# ETHERNET_PHY1.net
KiCad netlist of a schematic drawn in Altium Designer
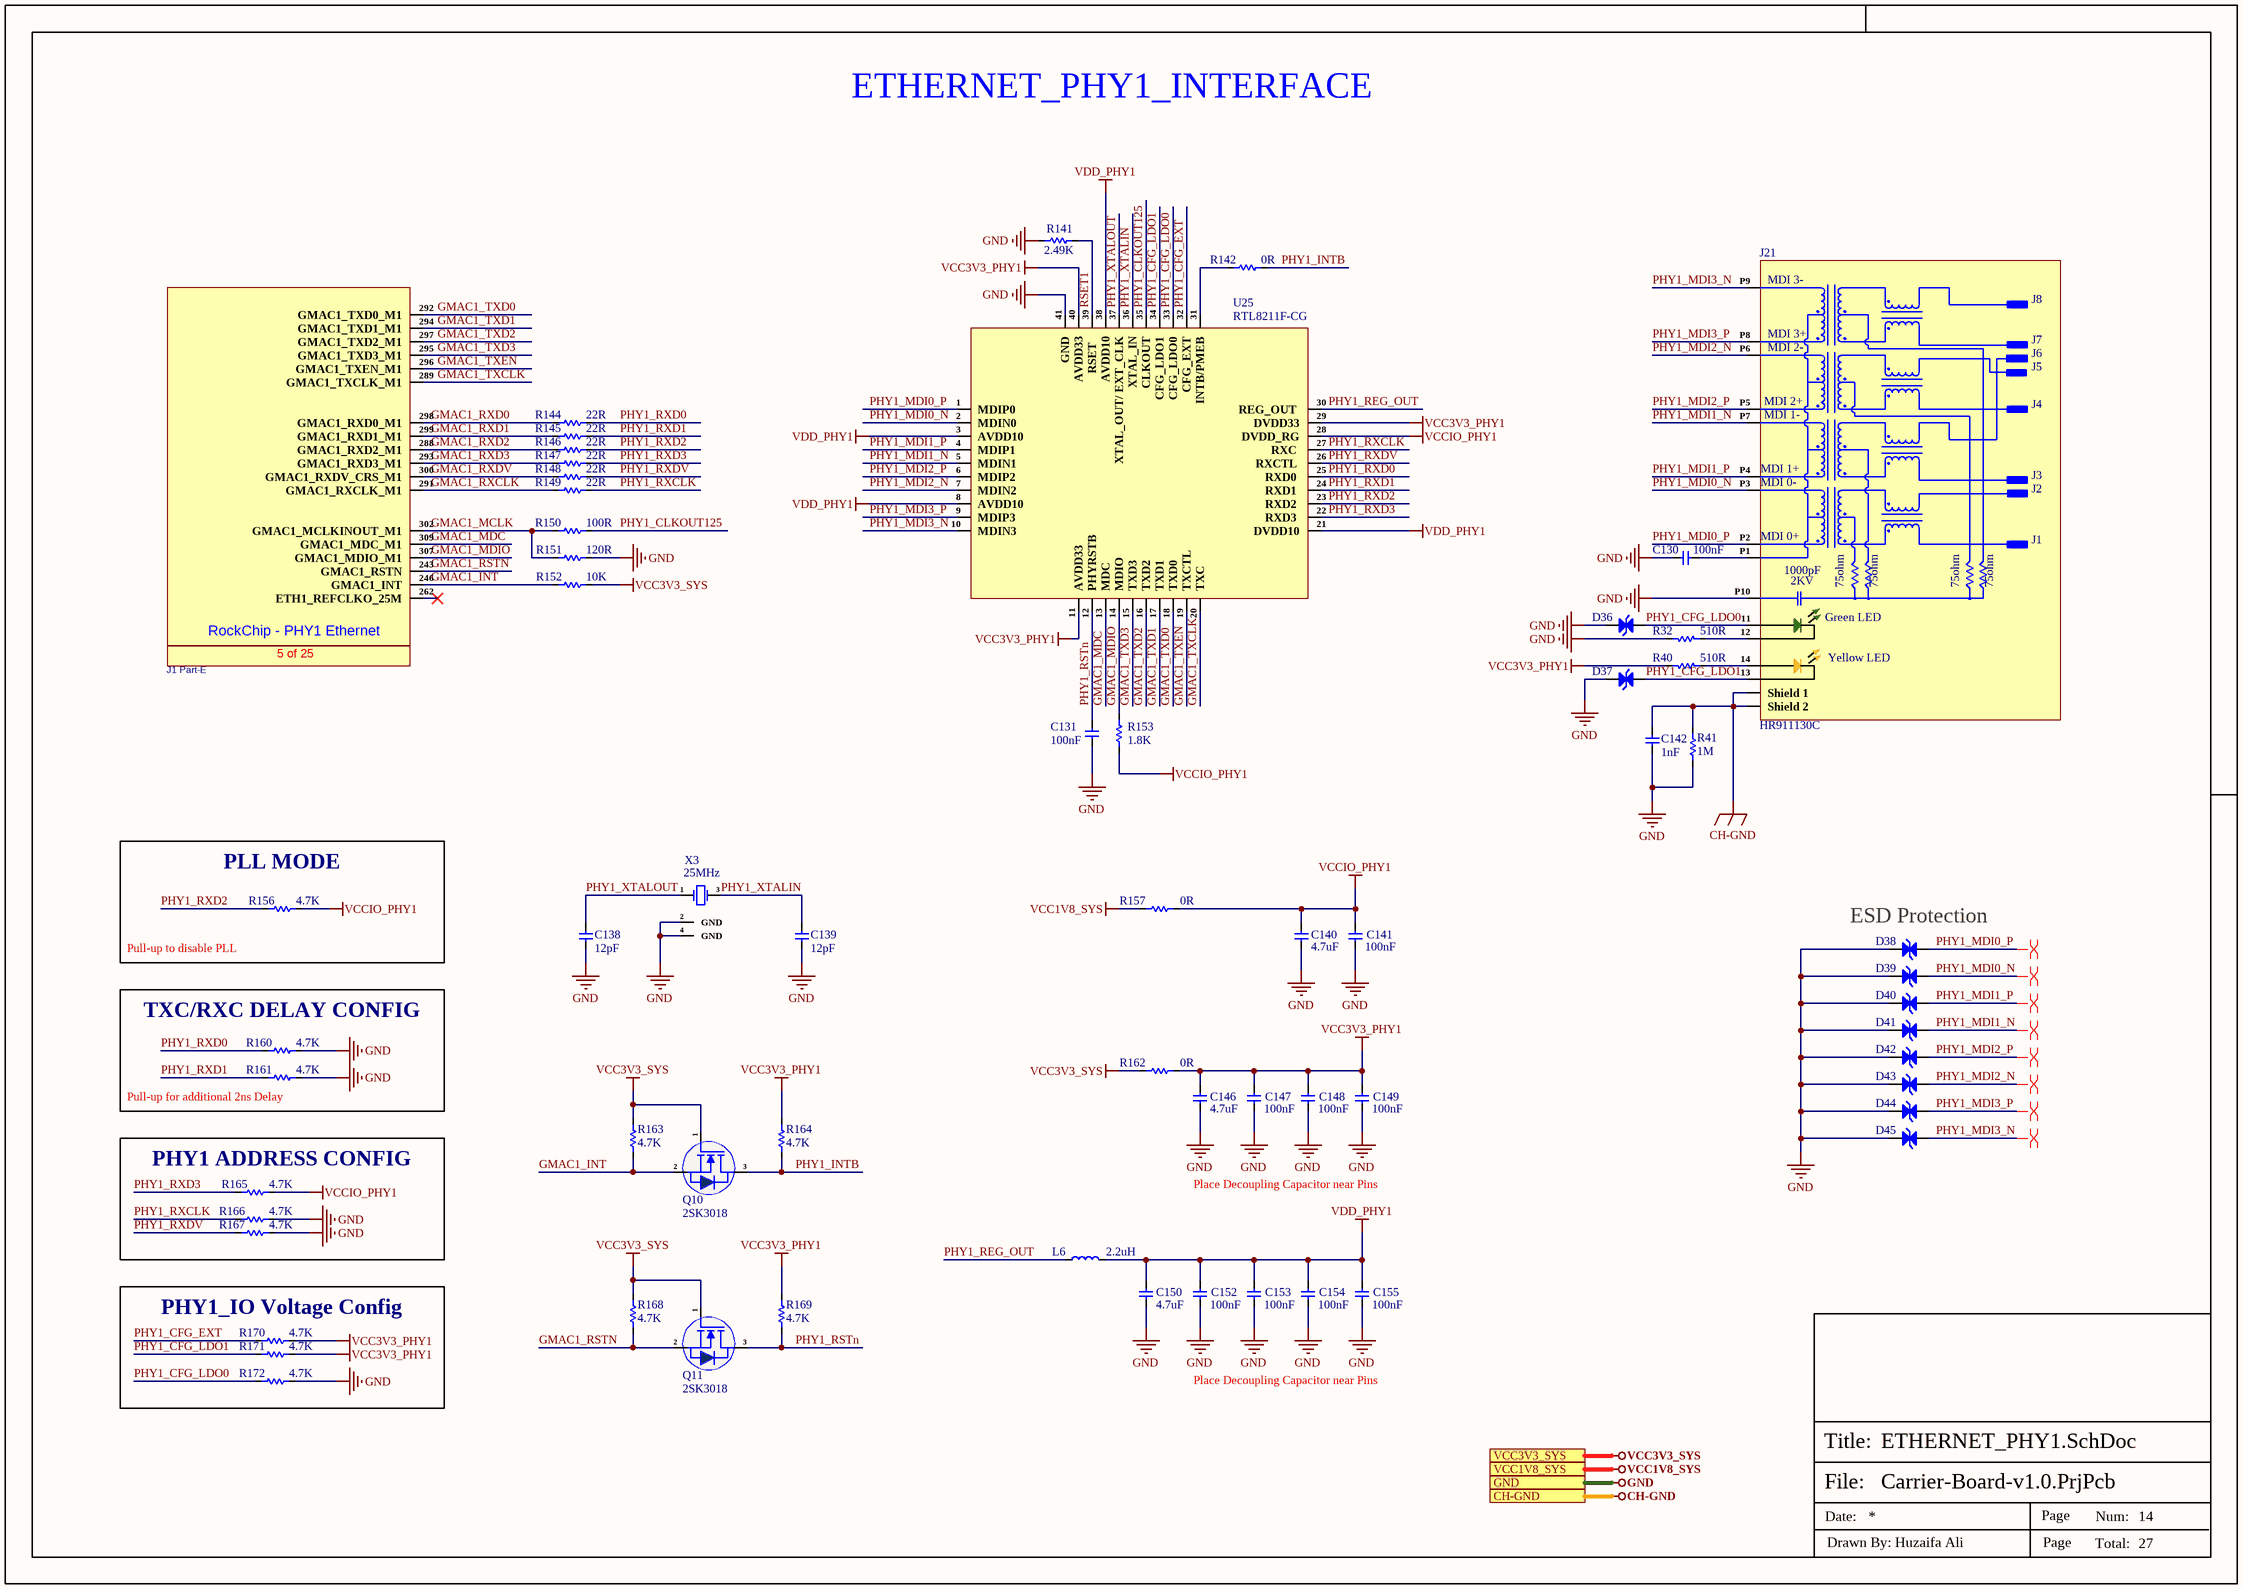
[diagram p0: ETHERNET_PHY1.SchDoc]

(export (version "E")
  (design (tool "Eeschema 10.0.6"))
  (components
    (comp (ref "C130")
      (value "100nF")
      (footprint "cap-0402")
      (description "CAP CER 0.1UF 50V X7R 0402")
      (fields
        (field (name "MANUFACTURER") "TDK")
        (field (name "MANUFACTURER PART NUMBER") "C1005X7R1H104KT000F")
      )
      (libsource (lib "eSpark Libraries") (part "C1005X7R1H104KT000F"))
    )
    (comp (ref "C131")
      (value "100nF")
      (footprint "Cap-0402")
      (description "CAP CER 0.1UF 16V X5R 0402")
      (fields
        (field (name "MANUFACTURER") "Yageo")
        (field (name "MANUFACTURER PART NUMBER") "CC0402KRX5R7BB104")
      )
      (libsource (lib "eSpark Libraries") (part "CC0402KRX5R7BB104"))
    )
    (comp (ref "C138")
      (value "12pF")
      (footprint "Cap-0402")
      (description "CAP CER 12PF 50V C0G/NP0 0402")
      (fields
        (field (name "MANUFACTURER") "Murata")
        (field (name "MANUFACTURER PART NUMBER") "GJM1555C1H120GB01D")
      )
      (libsource (lib "eSpark Libraries") (part "GJM1555C1H120GB01D"))
    )
    (comp (ref "C139")
      (value "12pF")
      (footprint "Cap-0402")
      (description "CAP CER 12PF 50V C0G/NP0 0402")
      (fields
        (field (name "MANUFACTURER") "Murata")
        (field (name "MANUFACTURER PART NUMBER") "GJM1555C1H120GB01D")
      )
      (libsource (lib "eSpark Libraries") (part "GJM1555C1H120GB01D"))
    )
    (comp (ref "C140")
      (value "4.7uF")
      (footprint "Cap-0402")
      (description "CAP CER 4.7UF 10V X5R 0402")
      (fields
        (field (name "MANUFACTURER") "Yageo")
        (field (name "MANUFACTURER PART NUMBER") "CC0402KRX5R6BB475")
      )
      (libsource (lib "eSpark Libraries") (part "CC0402KRX5R6BB475"))
    )
    (comp (ref "C141")
      (value "100nF")
      (footprint "Cap-0402")
      (description "CAP CER 0.1UF 16V X5R 0402")
      (fields
        (field (name "MANUFACTURER") "Yageo")
        (field (name "MANUFACTURER PART NUMBER") "CC0402KRX5R7BB104")
      )
      (libsource (lib "eSpark Libraries") (part "CC0402KRX5R7BB104"))
    )
    (comp (ref "C142")
      (value "1nF")
      (footprint "Cap-1206")
      (description "CAP CER 1000PF 2KV X7R 1206")
      (fields
        (field (name "MANUFACTURER") "Yageo")
        (field (name "MANUFACTURER PART NUMBER") "CC1206KKX7RDBB102")
      )
      (libsource (lib "eSpark Libraries") (part "CC1206KKX7RDBB102"))
    )
    (comp (ref "C146")
      (value "4.7uF")
      (footprint "Cap-0402")
      (description "CAP CER 4.7UF 10V X5R 0402")
      (fields
        (field (name "MANUFACTURER") "Yageo")
        (field (name "MANUFACTURER PART NUMBER") "CC0402KRX5R6BB475")
      )
      (libsource (lib "eSpark Libraries") (part "CC0402KRX5R6BB475"))
    )
    (comp (ref "C147")
      (value "100nF")
      (footprint "Cap-0402")
      (description "CAP CER 0.1UF 16V X5R 0402")
      (fields
        (field (name "MANUFACTURER") "Yageo")
        (field (name "MANUFACTURER PART NUMBER") "CC0402KRX5R7BB104")
      )
      (libsource (lib "eSpark Libraries") (part "CC0402KRX5R7BB104"))
    )
    (comp (ref "C148")
      (value "100nF")
      (footprint "Cap-0402")
      (description "CAP CER 0.1UF 16V X5R 0402")
      (fields
        (field (name "MANUFACTURER") "Yageo")
        (field (name "MANUFACTURER PART NUMBER") "CC0402KRX5R7BB104")
      )
      (libsource (lib "eSpark Libraries") (part "CC0402KRX5R7BB104"))
    )
    (comp (ref "C149")
      (value "100nF")
      (footprint "Cap-0402")
      (description "CAP CER 0.1UF 16V X5R 0402")
      (fields
        (field (name "MANUFACTURER") "Yageo")
        (field (name "MANUFACTURER PART NUMBER") "CC0402KRX5R7BB104")
      )
      (libsource (lib "eSpark Libraries") (part "CC0402KRX5R7BB104"))
    )
    (comp (ref "C150")
      (value "4.7uF")
      (footprint "Cap-0402")
      (description "CAP CER 4.7UF 10V X5R 0402")
      (fields
        (field (name "MANUFACTURER") "Yageo")
        (field (name "MANUFACTURER PART NUMBER") "CC0402KRX5R6BB475")
      )
      (libsource (lib "eSpark Libraries") (part "CC0402KRX5R6BB475"))
    )
    (comp (ref "C152")
      (value "100nF")
      (footprint "Cap-0402")
      (description "CAP CER 0.1UF 16V X5R 0402")
      (fields
        (field (name "MANUFACTURER") "Yageo")
        (field (name "MANUFACTURER PART NUMBER") "CC0402KRX5R7BB104")
      )
      (libsource (lib "eSpark Libraries") (part "CC0402KRX5R7BB104"))
    )
    (comp (ref "C153")
      (value "100nF")
      (footprint "Cap-0402")
      (description "CAP CER 0.1UF 16V X5R 0402")
      (fields
        (field (name "MANUFACTURER") "Yageo")
        (field (name "MANUFACTURER PART NUMBER") "CC0402KRX5R7BB104")
      )
      (libsource (lib "eSpark Libraries") (part "CC0402KRX5R7BB104"))
    )
    (comp (ref "C154")
      (value "100nF")
      (footprint "Cap-0402")
      (description "CAP CER 0.1UF 16V X5R 0402")
      (fields
        (field (name "MANUFACTURER") "Yageo")
        (field (name "MANUFACTURER PART NUMBER") "CC0402KRX5R7BB104")
      )
      (libsource (lib "eSpark Libraries") (part "CC0402KRX5R7BB104"))
    )
    (comp (ref "C155")
      (value "100nF")
      (footprint "Cap-0402")
      (description "CAP CER 0.1UF 16V X5R 0402")
      (fields
        (field (name "MANUFACTURER") "Yageo")
        (field (name "MANUFACTURER PART NUMBER") "CC0402KRX5R7BB104")
      )
      (libsource (lib "eSpark Libraries") (part "CC0402KRX5R7BB104"))
    )
    (comp (ref "D36")
      (value "ESD9X5VU")
      (footprint "DFN1006-2L_")
      (description "DFN1006-2 ESD Protection Devices ROHS")
      (fields (field (name "MANUFACTURER") "TECH PUBLIC") (field (name "LCSC PART NUMBER") "C2875160"))
      (libsource (lib "eSpark Libraries") (part "ESD9X5VU"))
    )
    (comp (ref "D37")
      (value "ESD9X5VU")
      (footprint "DFN1006-2L_")
      (description "DFN1006-2 ESD Protection Devices ROHS")
      (fields (field (name "MANUFACTURER") "TECH PUBLIC") (field (name "LCSC PART NUMBER") "C2875160"))
      (libsource (lib "eSpark Libraries") (part "ESD9X5VU"))
    )
    (comp (ref "D38")
      (value "ESD9X5VU")
      (footprint "DFN1006-2L_")
      (description "DFN1006-2 ESD Protection Devices ROHS")
      (fields (field (name "MANUFACTURER") "TECH PUBLIC") (field (name "LCSC PART NUMBER") "C2875160"))
      (libsource (lib "eSpark Libraries") (part "ESD9X5VU"))
    )
    (comp (ref "D39")
      (value "ESD9X5VU")
      (footprint "DFN1006-2L_")
      (description "DFN1006-2 ESD Protection Devices ROHS")
      (fields (field (name "MANUFACTURER") "TECH PUBLIC") (field (name "LCSC PART NUMBER") "C2875160"))
      (libsource (lib "eSpark Libraries") (part "ESD9X5VU"))
    )
    (comp (ref "D40")
      (value "ESD9X5VU")
      (footprint "DFN1006-2L_")
      (description "DFN1006-2 ESD Protection Devices ROHS")
      (fields (field (name "MANUFACTURER") "TECH PUBLIC") (field (name "LCSC PART NUMBER") "C2875160"))
      (libsource (lib "eSpark Libraries") (part "ESD9X5VU"))
    )
    (comp (ref "D41")
      (value "ESD9X5VU")
      (footprint "DFN1006-2L_")
      (description "DFN1006-2 ESD Protection Devices ROHS")
      (fields (field (name "MANUFACTURER") "TECH PUBLIC") (field (name "LCSC PART NUMBER") "C2875160"))
      (libsource (lib "eSpark Libraries") (part "ESD9X5VU"))
    )
    (comp (ref "D42")
      (value "ESD9X5VU")
      (footprint "DFN1006-2L_")
      (description "DFN1006-2 ESD Protection Devices ROHS")
      (fields (field (name "MANUFACTURER") "TECH PUBLIC") (field (name "LCSC PART NUMBER") "C2875160"))
      (libsource (lib "eSpark Libraries") (part "ESD9X5VU"))
    )
    (comp (ref "D43")
      (value "ESD9X5VU")
      (footprint "DFN1006-2L_")
      (description "DFN1006-2 ESD Protection Devices ROHS")
      (fields (field (name "MANUFACTURER") "TECH PUBLIC") (field (name "LCSC PART NUMBER") "C2875160"))
      (libsource (lib "eSpark Libraries") (part "ESD9X5VU"))
    )
    (comp (ref "D44")
      (value "ESD9X5VU")
      (footprint "DFN1006-2L_")
      (description "DFN1006-2 ESD Protection Devices ROHS")
      (fields (field (name "MANUFACTURER") "TECH PUBLIC") (field (name "LCSC PART NUMBER") "C2875160"))
      (libsource (lib "eSpark Libraries") (part "ESD9X5VU"))
    )
    (comp (ref "D45")
      (value "ESD9X5VU")
      (footprint "DFN1006-2L_")
      (description "DFN1006-2 ESD Protection Devices ROHS")
      (fields (field (name "MANUFACTURER") "TECH PUBLIC") (field (name "LCSC PART NUMBER") "C2875160"))
      (libsource (lib "eSpark Libraries") (part "ESD9X5VU"))
    )
    (comp (ref "J1 Part-")
      (value "AS0B826-S78B-7H")
      (footprint "AS0B826-S78B-7H")
      (description "SMD,P=0.5mm,Surface Mount，Right Angle")
      (fields (field (name "MANUFACTURER") "FOXCONN") (field (name "LCSC PART NUMBER") "C426232"))
      (libsource (lib "eSpark Libraries") (part "AS0B826-S78B-7H"))
    )
    (comp (ref "J21")
      (value "HR911130C")
      (footprint "HR911130C")
      (fields (field (name "MANUFACTURER") "HANRUN") (field (name "LCSC PART NUMBER") "C50933"))
      (libsource (lib "eSpark Libraries") (part "HR911130C"))
    )
    (comp (ref "L6")
      (value "2.2uH")
      (footprint "MAKK2016T2R2M_")
      (description "FIXED IND 2.2UH 1.5A 160MOHM SMD")
      (fields
        (field (name "MANUFACTURER") "Taiyo Yuden")
        (field (name "MANUFACTURER PART NUMBER") "MAKK2016T2R2M")
      )
      (libsource (lib "eSpark Libraries") (part "MAKK2016T2R2M"))
    )
    (comp (ref "Q10")
      (value "2SK3018")
      (footprint "SOT-23")
      (description "30V 100mA 200mW 8Ω@4V,10mA N Channel SOT-23 MOSFETs ROHS")
      (fields (field (name "MANUFACTURER") "KUU") (field (name "LCSC PART NUMBER") "C2944164"))
      (libsource (lib "eSpark Libraries") (part "2SK3018"))
    )
    (comp (ref "Q11")
      (value "2SK3018")
      (footprint "SOT-23")
      (description "30V 100mA 200mW 8Ω@4V,10mA N Channel SOT-23 MOSFETs ROHS")
      (fields (field (name "MANUFACTURER") "KUU") (field (name "LCSC PART NUMBER") "C2944164"))
      (libsource (lib "eSpark Libraries") (part "2SK3018"))
    )
    (comp (ref "R32")
      (value "510R")
      (footprint "Res-0402")
      (description "RES SMD 510 OHM 1% 1/16W 0402")
      (fields
        (field (name "MANUFACTURER") "Yageo")
        (field (name "MANUFACTURER PART NUMBER") "RT0402FRE07510RL")
      )
      (libsource (lib "eSpark Libraries") (part "RT0402FRE07510RL"))
    )
    (comp (ref "R40")
      (value "510R")
      (footprint "Res-0402")
      (description "RES SMD 510 OHM 1% 1/16W 0402")
      (fields
        (field (name "MANUFACTURER") "Yageo")
        (field (name "MANUFACTURER PART NUMBER") "RT0402FRE07510RL")
      )
      (libsource (lib "eSpark Libraries") (part "RT0402FRE07510RL"))
    )
    (comp (ref "R41")
      (value "1M")
      (footprint "Res-0402")
      (description "RES SMD 1M OHM 5% 1/16W 0402")
      (fields
        (field (name "MANUFACTURER") "Yageo")
        (field (name "MANUFACTURER PART NUMBER") "AF0402JR-071ML")
      )
      (libsource (lib "eSpark Libraries") (part "AF0402JR-071ML"))
    )
    (comp (ref "R141")
      (value "2.49K")
      (footprint "Res-0402")
      (description "RES 2.49K OHM 1% 1/16W 0402")
      (fields
        (field (name "MANUFACTURER") "Yageo")
        (field (name "MANUFACTURER PART NUMBER") "RC0402FR-072K49L")
      )
      (libsource (lib "eSpark Libraries") (part "RC0402FR-072K49L"))
    )
    (comp (ref "R142")
      (value "0R")
      (footprint "Res-0402")
      (description "RES 0 OHM JUMPER 1/16W 0402")
      (fields
        (field (name "MANUFACTURER") "Yageo")
        (field (name "MANUFACTURER PART NUMBER") "RC0402FR-070RL")
      )
      (libsource (lib "eSpark Libraries") (part "RC0402FR-070RL"))
    )
    (comp (ref "R144")
      (value "22R")
      (footprint "Res-0402")
      (description "RES 22 OHM 1% 1/16W 0402")
      (fields
        (field (name "MANUFACTURER") "Yageo")
        (field (name "MANUFACTURER PART NUMBER") "RC0402FR-0722RL")
      )
      (libsource (lib "eSpark Libraries") (part "RC0402FR-0722RL"))
    )
    (comp (ref "R145")
      (value "22R")
      (footprint "Res-0402")
      (description "RES 22 OHM 1% 1/16W 0402")
      (fields
        (field (name "MANUFACTURER") "Yageo")
        (field (name "MANUFACTURER PART NUMBER") "RC0402FR-0722RL")
      )
      (libsource (lib "eSpark Libraries") (part "RC0402FR-0722RL"))
    )
    (comp (ref "R146")
      (value "22R")
      (footprint "Res-0402")
      (description "RES 22 OHM 1% 1/16W 0402")
      (fields
        (field (name "MANUFACTURER") "Yageo")
        (field (name "MANUFACTURER PART NUMBER") "RC0402FR-0722RL")
      )
      (libsource (lib "eSpark Libraries") (part "RC0402FR-0722RL"))
    )
    (comp (ref "R147")
      (value "22R")
      (footprint "Res-0402")
      (description "RES 22 OHM 1% 1/16W 0402")
      (fields
        (field (name "MANUFACTURER") "Yageo")
        (field (name "MANUFACTURER PART NUMBER") "RC0402FR-0722RL")
      )
      (libsource (lib "eSpark Libraries") (part "RC0402FR-0722RL"))
    )
    (comp (ref "R148")
      (value "22R")
      (footprint "Res-0402")
      (description "RES 22 OHM 1% 1/16W 0402")
      (fields
        (field (name "MANUFACTURER") "Yageo")
        (field (name "MANUFACTURER PART NUMBER") "RC0402FR-0722RL")
      )
      (libsource (lib "eSpark Libraries") (part "RC0402FR-0722RL"))
    )
    (comp (ref "R149")
      (value "22R")
      (footprint "Res-0402")
      (description "RES 22 OHM 1% 1/16W 0402")
      (fields
        (field (name "MANUFACTURER") "Yageo")
        (field (name "MANUFACTURER PART NUMBER") "RC0402FR-0722RL")
      )
      (libsource (lib "eSpark Libraries") (part "RC0402FR-0722RL"))
    )
    (comp (ref "R150")
      (value "100R")
      (footprint "Res-0402")
      (description "RES 100 OHM 1% 1/16W 0402")
      (fields
        (field (name "MANUFACTURER") "Yageo")
        (field (name "MANUFACTURER PART NUMBER") "RC0402FR-07100RL")
      )
      (libsource (lib "eSpark Libraries") (part "RC0402FR-07100RL"))
    )
    (comp (ref "R151")
      (value "120R")
      (footprint "Res-0402")
      (description "RES 120 OHM 1% 1/16W 0402")
      (fields
        (field (name "MANUFACTURER") "Yageo")
        (field (name "MANUFACTURER PART NUMBER") "RC0402FR-07120RL")
      )
      (libsource (lib "eSpark Libraries") (part "RC0402FR-07120RL"))
    )
    (comp (ref "R152")
      (value "10K")
      (footprint "Res-0402")
      (description "RES 10K OHM 1% 1/16W 0402")
      (fields
        (field (name "MANUFACTURER") "Yageo")
        (field (name "MANUFACTURER PART NUMBER") "RC0402FR-0710KL")
      )
      (libsource (lib "eSpark Libraries") (part "RC0402FR-0710KL"))
    )
    (comp (ref "R153")
      (value "1.8K")
      (footprint "Res-0402")
      (description "RES SMD 1.8K OHM 1% 1/5W 0402")
      (fields
        (field (name "MANUFACTURER") "Vishay Dale")
        (field (name "MANUFACTURER PART NUMBER") "RCS04021K80FKED")
      )
      (libsource (lib "eSpark Libraries") (part "RCS04021K80FKED"))
    )
    (comp (ref "R156")
      (value "4.7K")
      (footprint "Res-0402")
      (description "RES 4.7K OHM 1% 1/16W 0402")
      (fields
        (field (name "MANUFACTURER") "Yageo")
        (field (name "MANUFACTURER PART NUMBER") "RC0402FR-074K7L")
      )
      (libsource (lib "eSpark Libraries") (part "RC0402FR-074K7L"))
    )
    (comp (ref "R157")
      (value "0R")
      (footprint "Res-0603")
      (description "RES 0 OHM JUMPER 1/10W 0603")
      (fields
        (field (name "MANUFACTURER") "Yageo")
        (field (name "MANUFACTURER PART NUMBER") "RC0603JR-070RL")
      )
      (libsource (lib "eSpark Libraries") (part "RC0603JR-070RL"))
    )
    (comp (ref "R160")
      (value "4.7K")
      (footprint "Res-0402")
      (description "RES 4.7K OHM 1% 1/16W 0402")
      (fields
        (field (name "MANUFACTURER") "Yageo")
        (field (name "MANUFACTURER PART NUMBER") "RC0402FR-074K7L")
      )
      (libsource (lib "eSpark Libraries") (part "RC0402FR-074K7L"))
    )
    (comp (ref "R161")
      (value "4.7K")
      (footprint "Res-0402")
      (description "RES 4.7K OHM 1% 1/16W 0402")
      (fields
        (field (name "MANUFACTURER") "Yageo")
        (field (name "MANUFACTURER PART NUMBER") "RC0402FR-074K7L")
      )
      (libsource (lib "eSpark Libraries") (part "RC0402FR-074K7L"))
    )
    (comp (ref "R162")
      (value "0R")
      (footprint "Res-0603")
      (description "RES 0 OHM JUMPER 1/10W 0603")
      (fields
        (field (name "MANUFACTURER") "Yageo")
        (field (name "MANUFACTURER PART NUMBER") "RC0603JR-070RL")
      )
      (libsource (lib "eSpark Libraries") (part "RC0603JR-070RL"))
    )
    (comp (ref "R163")
      (value "4.7K")
      (footprint "Res-0402")
      (description "RES 4.7K OHM 1% 1/16W 0402")
      (fields
        (field (name "MANUFACTURER") "Yageo")
        (field (name "MANUFACTURER PART NUMBER") "RC0402FR-074K7L")
      )
      (libsource (lib "eSpark Libraries") (part "RC0402FR-074K7L"))
    )
    (comp (ref "R164")
      (value "4.7K")
      (footprint "Res-0402")
      (description "RES 4.7K OHM 1% 1/16W 0402")
      (fields
        (field (name "MANUFACTURER") "Yageo")
        (field (name "MANUFACTURER PART NUMBER") "RC0402FR-074K7L")
      )
      (libsource (lib "eSpark Libraries") (part "RC0402FR-074K7L"))
    )
    (comp (ref "R165")
      (value "4.7K")
      (footprint "Res-0402")
      (description "RES 4.7K OHM 1% 1/16W 0402")
      (fields
        (field (name "MANUFACTURER") "Yageo")
        (field (name "MANUFACTURER PART NUMBER") "RC0402FR-074K7L")
      )
      (libsource (lib "eSpark Libraries") (part "RC0402FR-074K7L"))
    )
    (comp (ref "R166")
      (value "4.7K")
      (footprint "Res-0402")
      (description "RES 4.7K OHM 1% 1/16W 0402")
      (fields
        (field (name "MANUFACTURER") "Yageo")
        (field (name "MANUFACTURER PART NUMBER") "RC0402FR-074K7L")
      )
      (libsource (lib "eSpark Libraries") (part "RC0402FR-074K7L"))
    )
    (comp (ref "R167")
      (value "4.7K")
      (footprint "Res-0402")
      (description "RES 4.7K OHM 1% 1/16W 0402")
      (fields
        (field (name "MANUFACTURER") "Yageo")
        (field (name "MANUFACTURER PART NUMBER") "RC0402FR-074K7L")
      )
      (libsource (lib "eSpark Libraries") (part "RC0402FR-074K7L"))
    )
    (comp (ref "R168")
      (value "4.7K")
      (footprint "Res-0402")
      (description "RES 4.7K OHM 1% 1/16W 0402")
      (fields
        (field (name "MANUFACTURER") "Yageo")
        (field (name "MANUFACTURER PART NUMBER") "RC0402FR-074K7L")
      )
      (libsource (lib "eSpark Libraries") (part "RC0402FR-074K7L"))
    )
    (comp (ref "R169")
      (value "4.7K")
      (footprint "Res-0402")
      (description "RES 4.7K OHM 1% 1/16W 0402")
      (fields
        (field (name "MANUFACTURER") "Yageo")
        (field (name "MANUFACTURER PART NUMBER") "RC0402FR-074K7L")
      )
      (libsource (lib "eSpark Libraries") (part "RC0402FR-074K7L"))
    )
    (comp (ref "R170")
      (value "4.7K")
      (footprint "Res-0402")
      (description "RES 4.7K OHM 1% 1/16W 0402")
      (fields
        (field (name "MANUFACTURER") "Yageo")
        (field (name "MANUFACTURER PART NUMBER") "RC0402FR-074K7L")
      )
      (libsource (lib "eSpark Libraries") (part "RC0402FR-074K7L"))
    )
    (comp (ref "R171")
      (value "4.7K")
      (footprint "Res-0402")
      (description "RES 4.7K OHM 1% 1/16W 0402")
      (fields
        (field (name "MANUFACTURER") "Yageo")
        (field (name "MANUFACTURER PART NUMBER") "RC0402FR-074K7L")
      )
      (libsource (lib "eSpark Libraries") (part "RC0402FR-074K7L"))
    )
    (comp (ref "R172")
      (value "4.7K")
      (footprint "Res-0402")
      (description "RES 4.7K OHM 1% 1/16W 0402")
      (fields
        (field (name "MANUFACTURER") "Yageo")
        (field (name "MANUFACTURER PART NUMBER") "RC0402FR-074K7L")
      )
      (libsource (lib "eSpark Libraries") (part "RC0402FR-074K7L"))
    )
    (comp (ref "U25")
      (value "RTL8211F-CG")
      (footprint "WQFN-40-EP(5x5)")
      (description "WQFN-40-EP(5x5) Ethernet ICs ROHS")
      (fields (field (name "MANUFACTURER") "Realtek Semicon") (field (name "LCSC PART NUMBER") "C187932"))
      (libsource (lib "eSpark Libraries") (part "RTL8211F-CG"))
    )
    (comp (ref "X3")
      (value "25MHz")
      (footprint "Q22FA12800090")
      (description "CRYSTAL 25.0000MHZ 12PF SMD")
      (fields
        (field (name "MANUFACTURER") "Seiko Epson")
        (field (name "MANUFACTURER PART NUMBER") "Q22FA12800090")
      )
      (libsource (lib "eSpark Libraries") (part "Q22FA12800090"))
    )
  )
  (nets
    (net (code "1") (name "/GMAC1_INT") (class "Default")
      (node (ref "J1 Part-") (pin "246") (pinfunction "GMAC1_INT_246") (pintype "passive"))
      (node (ref "Q10") (pin "2") (pinfunction "S_2") (pintype "passive"))
      (node (ref "R152") (pin "2") (pinfunction "2_2") (pintype "passive"))
      (node (ref "R163") (pin "1") (pinfunction "1_1") (pintype "passive"))
    )
    (net (code "2") (name "/GMAC1_MCLK") (class "Default")
      (node (ref "J1 Part-") (pin "302") (pinfunction "GMAC1_MCLKINOUT_M1_302") (pintype "passive"))
      (node (ref "R150") (pin "1") (pinfunction "1_1") (pintype "passive"))
      (node (ref "R151") (pin "2") (pinfunction "2_2") (pintype "passive"))
    )
    (net (code "3") (name "/GMAC1_MDC") (class "Default")
      (node (ref "J1 Part-") (pin "309") (pinfunction "GMAC1_MDC_M1_309") (pintype "passive"))
      (node (ref "U25") (pin "13") (pinfunction "MDC_13") (pintype "passive"))
    )
    (net (code "4") (name "/GMAC1_MDIO") (class "Default")
      (node (ref "J1 Part-") (pin "307") (pinfunction "GMAC1_MDIO_M1_307") (pintype "passive"))
      (node (ref "R153") (pin "1") (pinfunction "1_1") (pintype "passive"))
      (node (ref "U25") (pin "14") (pinfunction "MDIO_14") (pintype "passive"))
    )
    (net (code "5") (name "/GMAC1_RSTN") (class "Default")
      (node (ref "J1 Part-") (pin "243") (pinfunction "GMAC1_RSTN_243") (pintype "passive"))
      (node (ref "Q11") (pin "2") (pinfunction "S_2") (pintype "passive"))
      (node (ref "R168") (pin "1") (pinfunction "1_1") (pintype "passive"))
    )
    (net (code "6") (name "/GMAC1_RXCLK") (class "Default")
      (node (ref "J1 Part-") (pin "291") (pinfunction "GMAC1_RXCLK_M1_291") (pintype "passive"))
      (node (ref "R149") (pin "1") (pinfunction "1_1") (pintype "passive"))
    )
    (net (code "7") (name "/GMAC1_RXD0") (class "Default")
      (node (ref "J1 Part-") (pin "298") (pinfunction "GMAC1_RXD0_M1_298") (pintype "passive"))
      (node (ref "R144") (pin "1") (pinfunction "1_1") (pintype "passive"))
    )
    (net (code "8") (name "/GMAC1_RXD1") (class "Default")
      (node (ref "J1 Part-") (pin "299") (pinfunction "GMAC1_RXD1_M1_299") (pintype "passive"))
      (node (ref "R145") (pin "1") (pinfunction "1_1") (pintype "passive"))
    )
    (net (code "9") (name "/GMAC1_RXD2") (class "Default")
      (node (ref "J1 Part-") (pin "288") (pinfunction "GMAC1_RXD2_M1_288") (pintype "passive"))
      (node (ref "R146") (pin "1") (pinfunction "1_1") (pintype "passive"))
    )
    (net (code "10") (name "/GMAC1_RXD3") (class "Default")
      (node (ref "J1 Part-") (pin "293") (pinfunction "GMAC1_RXD3_M1_293") (pintype "passive"))
      (node (ref "R147") (pin "1") (pinfunction "1_1") (pintype "passive"))
    )
    (net (code "11") (name "/GMAC1_RXDV") (class "Default")
      (node (ref "J1 Part-") (pin "300") (pinfunction "GMAC1_RXDV_CRS_M1_300") (pintype "passive"))
      (node (ref "R148") (pin "1") (pinfunction "1_1") (pintype "passive"))
    )
    (net (code "12") (name "/GMAC1_TXCLK") (class "Default")
      (node (ref "J1 Part-") (pin "289") (pinfunction "GMAC1_TXCLK_M1_289") (pintype "passive"))
      (node (ref "U25") (pin "20") (pinfunction "TXC_20") (pintype "passive"))
    )
    (net (code "13") (name "/GMAC1_TXD0") (class "Default")
      (node (ref "J1 Part-") (pin "292") (pinfunction "GMAC1_TXD0_M1_292") (pintype "passive"))
      (node (ref "U25") (pin "18") (pinfunction "TXD0_18") (pintype "passive"))
    )
    (net (code "14") (name "/GMAC1_TXD1") (class "Default")
      (node (ref "J1 Part-") (pin "294") (pinfunction "GMAC1_TXD1_M1_294") (pintype "passive"))
      (node (ref "U25") (pin "17") (pinfunction "TXD1_17") (pintype "passive"))
    )
    (net (code "15") (name "/GMAC1_TXD2") (class "Default")
      (node (ref "J1 Part-") (pin "297") (pinfunction "GMAC1_TXD2_M1_297") (pintype "passive"))
      (node (ref "U25") (pin "16") (pinfunction "TXD2_16") (pintype "passive"))
    )
    (net (code "16") (name "/GMAC1_TXD3") (class "Default")
      (node (ref "J1 Part-") (pin "295") (pinfunction "GMAC1_TXD3_M1_295") (pintype "passive"))
      (node (ref "U25") (pin "15") (pinfunction "TXD3_15") (pintype "passive"))
    )
    (net (code "17") (name "/GMAC1_TXEN") (class "Default")
      (node (ref "J1 Part-") (pin "296") (pinfunction "GMAC1_TXEN_M1_296") (pintype "passive"))
      (node (ref "U25") (pin "19") (pinfunction "TXCTL_19") (pintype "passive"))
    )
    (net (code "18") (name "/PHY1_CFG_EXT") (class "Default")
      (node (ref "R170") (pin "1") (pinfunction "1_1") (pintype "passive"))
      (node (ref "U25") (pin "32") (pinfunction "CFG_EXT_32") (pintype "passive"))
    )
    (net (code "19") (name "/PHY1_CFG_LDO0") (class "Default")
      (node (ref "D36") (pin "2") (pinfunction "A_2") (pintype "passive"))
      (node (ref "J21") (pin "11") (pintype "passive"))
      (node (ref "R172") (pin "1") (pinfunction "1_1") (pintype "passive"))
      (node (ref "U25") (pin "33") (pinfunction "CFG_LDO0_33") (pintype "passive"))
    )
    (net (code "20") (name "/PHY1_CFG_LDO1") (class "Default")
      (node (ref "D37") (pin "2") (pinfunction "A_2") (pintype "passive"))
      (node (ref "J21") (pin "13") (pintype "passive"))
      (node (ref "R171") (pin "1") (pinfunction "1_1") (pintype "passive"))
      (node (ref "U25") (pin "34") (pinfunction "CFG_LDO1_34") (pintype "passive"))
    )
    (net (code "21") (name "/PHY1_CLKOUT125") (class "Default")
      (node (ref "R150") (pin "2") (pinfunction "2_2") (pintype "passive"))
      (node (ref "U25") (pin "35") (pinfunction "CLKOUT_35") (pintype "passive"))
    )
    (net (code "22") (name "/PHY1_INTB") (class "Default")
      (node (ref "Q10") (pin "3") (pinfunction "D_3") (pintype "passive"))
      (node (ref "R142") (pin "2") (pinfunction "2_2") (pintype "passive"))
      (node (ref "R164") (pin "1") (pinfunction "1_1") (pintype "passive"))
    )
    (net (code "23") (name "/PHY1_MDI0_N") (class "Default")
      (node (ref "D39") (pin "2") (pinfunction "A_2") (pintype "passive"))
      (node (ref "J21") (pin "P3") (pinfunction "P4_P3") (pintype "passive"))
      (node (ref "U25") (pin "2") (pinfunction "MDIN0_2") (pintype "passive"))
    )
    (net (code "24") (name "/PHY1_MDI0_P") (class "Default")
      (node (ref "D38") (pin "2") (pinfunction "A_2") (pintype "passive"))
      (node (ref "J21") (pin "P2") (pinfunction "P2_P2") (pintype "passive"))
      (node (ref "U25") (pin "1") (pinfunction "MDIP0_1") (pintype "passive"))
    )
    (net (code "25") (name "/PHY1_MDI1_N") (class "Default")
      (node (ref "D41") (pin "2") (pinfunction "A_2") (pintype "passive"))
      (node (ref "J21") (pin "P7") (pinfunction "P7_P7") (pintype "passive"))
      (node (ref "U25") (pin "5") (pinfunction "MDIN1_5") (pintype "passive"))
    )
    (net (code "26") (name "/PHY1_MDI1_P") (class "Default")
      (node (ref "D40") (pin "2") (pinfunction "A_2") (pintype "passive"))
      (node (ref "J21") (pin "P4") (pinfunction "P4_P4") (pintype "passive"))
      (node (ref "U25") (pin "4") (pinfunction "MDIP1_4") (pintype "passive"))
    )
    (net (code "27") (name "/PHY1_MDI2_N") (class "Default")
      (node (ref "D43") (pin "2") (pinfunction "A_2") (pintype "passive"))
      (node (ref "J21") (pin "P6") (pinfunction "P6_P6") (pintype "passive"))
      (node (ref "U25") (pin "7") (pinfunction "MDIN2_7") (pintype "passive"))
    )
    (net (code "28") (name "/PHY1_MDI2_P") (class "Default")
      (node (ref "D42") (pin "2") (pinfunction "A_2") (pintype "passive"))
      (node (ref "J21") (pin "P5") (pinfunction "P5_P5") (pintype "passive"))
      (node (ref "U25") (pin "6") (pinfunction "MDIP2_6") (pintype "passive"))
    )
    (net (code "29") (name "/PHY1_MDI3_N") (class "Default")
      (node (ref "D45") (pin "2") (pinfunction "A_2") (pintype "passive"))
      (node (ref "J21") (pin "P9") (pinfunction "P9_P9") (pintype "passive"))
      (node (ref "U25") (pin "10") (pinfunction "MDIN3_10") (pintype "passive"))
    )
    (net (code "30") (name "/PHY1_MDI3_P") (class "Default")
      (node (ref "D44") (pin "2") (pinfunction "A_2") (pintype "passive"))
      (node (ref "J21") (pin "P8") (pinfunction "P8_P8") (pintype "passive"))
      (node (ref "U25") (pin "9") (pinfunction "MDIP3_9") (pintype "passive"))
    )
    (net (code "31") (name "/PHY1_REG_OUT") (class "Default")
      (node (ref "L6") (pin "1") (pinfunction "1_1") (pintype "passive"))
      (node (ref "U25") (pin "30") (pinfunction "REG_OUT_30") (pintype "passive"))
    )
    (net (code "32") (name "/PHY1_RSTn") (class "Default")
      (node (ref "C131") (pin "2") (pinfunction "2_2") (pintype "passive"))
      (node (ref "Q11") (pin "3") (pinfunction "D_3") (pintype "passive"))
      (node (ref "R169") (pin "1") (pinfunction "1_1") (pintype "passive"))
      (node (ref "U25") (pin "12") (pinfunction "PHYRSTB_12") (pintype "passive"))
    )
    (net (code "33") (name "/PHY1_RXCLK") (class "Default")
      (node (ref "R149") (pin "2") (pinfunction "2_2") (pintype "passive"))
      (node (ref "R166") (pin "1") (pinfunction "1_1") (pintype "passive"))
      (node (ref "U25") (pin "27") (pinfunction "RXC_27") (pintype "passive"))
    )
    (net (code "34") (name "/PHY1_RXD0") (class "Default")
      (node (ref "R144") (pin "2") (pinfunction "2_2") (pintype "passive"))
      (node (ref "R160") (pin "1") (pinfunction "1_1") (pintype "passive"))
      (node (ref "U25") (pin "25") (pinfunction "RXD0_25") (pintype "passive"))
    )
    (net (code "35") (name "/PHY1_RXD1") (class "Default")
      (node (ref "R145") (pin "2") (pinfunction "2_2") (pintype "passive"))
      (node (ref "R161") (pin "1") (pinfunction "1_1") (pintype "passive"))
      (node (ref "U25") (pin "24") (pinfunction "RXD1_24") (pintype "passive"))
    )
    (net (code "36") (name "/PHY1_RXD2") (class "Default")
      (node (ref "R146") (pin "2") (pinfunction "2_2") (pintype "passive"))
      (node (ref "R156") (pin "1") (pinfunction "1_1") (pintype "passive"))
      (node (ref "U25") (pin "23") (pinfunction "RXD2_23") (pintype "passive"))
    )
    (net (code "37") (name "/PHY1_RXD3") (class "Default")
      (node (ref "R147") (pin "2") (pinfunction "2_2") (pintype "passive"))
      (node (ref "R165") (pin "1") (pinfunction "1_1") (pintype "passive"))
      (node (ref "U25") (pin "22") (pinfunction "RXD3_22") (pintype "passive"))
    )
    (net (code "38") (name "/PHY1_RXDV") (class "Default")
      (node (ref "R148") (pin "2") (pinfunction "2_2") (pintype "passive"))
      (node (ref "R167") (pin "1") (pinfunction "1_1") (pintype "passive"))
      (node (ref "U25") (pin "26") (pinfunction "RXCTL_26") (pintype "passive"))
    )
    (net (code "39") (name "/PHY1_XTALIN") (class "Default")
      (node (ref "C139") (pin "2") (pinfunction "2_2") (pintype "passive"))
      (node (ref "U25") (pin "36") (pinfunction "XTAL_IN_36") (pintype "passive"))
      (node (ref "X3") (pin "3") (pinfunction "OSC2_3") (pintype "passive"))
    )
    (net (code "40") (name "/PHY1_XTALOUT") (class "Default")
      (node (ref "C138") (pin "2") (pinfunction "2_2") (pintype "passive"))
      (node (ref "U25") (pin "37") (pinfunction "XTAL_OUT/_EXT_CLK_37") (pintype "passive"))
      (node (ref "X3") (pin "1") (pinfunction "OSC1_1") (pintype "passive"))
    )
    (net (code "41") (name "/RSET1") (class "Default")
      (node (ref "R141") (pin "2") (pinfunction "2_2") (pintype "passive"))
      (node (ref "U25") (pin "39") (pinfunction "RSET_39") (pintype "passive"))
    )
    (net (code "42") (name "CH-GND") (class "Default")
      (node (ref "C142") (pin "2") (pinfunction "2_2") (pintype "passive"))
      (node (ref "J21") (pin "SH1") (pinfunction "Shield_1_SH1") (pintype "passive"))
      (node (ref "J21") (pin "SH2") (pinfunction "Shield_2_SH2") (pintype "passive"))
      (node (ref "R41") (pin "2") (pinfunction "2_2") (pintype "passive"))
    )
    (net (code "43") (name "GND") (class "Default")
      (node (ref "C130") (pin "1") (pinfunction "1_1") (pintype "passive"))
      (node (ref "C131") (pin "1") (pinfunction "1_1") (pintype "passive"))
      (node (ref "C138") (pin "1") (pinfunction "1_1") (pintype "passive"))
      (node (ref "C139") (pin "1") (pinfunction "1_1") (pintype "passive"))
      (node (ref "C140") (pin "1") (pinfunction "1_1") (pintype "passive"))
      (node (ref "C141") (pin "1") (pinfunction "1_1") (pintype "passive"))
      (node (ref "C142") (pin "1") (pinfunction "1_1") (pintype "passive"))
      (node (ref "C146") (pin "1") (pinfunction "1_1") (pintype "passive"))
      (node (ref "C147") (pin "1") (pinfunction "1_1") (pintype "passive"))
      (node (ref "C148") (pin "1") (pinfunction "1_1") (pintype "passive"))
      (node (ref "C149") (pin "1") (pinfunction "1_1") (pintype "passive"))
      (node (ref "C150") (pin "1") (pinfunction "1_1") (pintype "passive"))
      (node (ref "C152") (pin "1") (pinfunction "1_1") (pintype "passive"))
      (node (ref "C153") (pin "1") (pinfunction "1_1") (pintype "passive"))
      (node (ref "C154") (pin "1") (pinfunction "1_1") (pintype "passive"))
      (node (ref "C155") (pin "1") (pinfunction "1_1") (pintype "passive"))
      (node (ref "D36") (pin "1") (pinfunction "A_1") (pintype "passive"))
      (node (ref "D37") (pin "1") (pinfunction "A_1") (pintype "passive"))
      (node (ref "D38") (pin "1") (pinfunction "A_1") (pintype "passive"))
      (node (ref "D39") (pin "1") (pinfunction "A_1") (pintype "passive"))
      (node (ref "D40") (pin "1") (pinfunction "A_1") (pintype "passive"))
      (node (ref "D41") (pin "1") (pinfunction "A_1") (pintype "passive"))
      (node (ref "D42") (pin "1") (pinfunction "A_1") (pintype "passive"))
      (node (ref "D43") (pin "1") (pinfunction "A_1") (pintype "passive"))
      (node (ref "D44") (pin "1") (pinfunction "A_1") (pintype "passive"))
      (node (ref "D45") (pin "1") (pinfunction "A_1") (pintype "passive"))
      (node (ref "J21") (pin "P10") (pinfunction "P10_P10") (pintype "power_in"))
      (node (ref "R141") (pin "1") (pinfunction "1_1") (pintype "passive"))
      (node (ref "R151") (pin "1") (pinfunction "1_1") (pintype "passive"))
      (node (ref "R160") (pin "2") (pinfunction "2_2") (pintype "passive"))
      (node (ref "R161") (pin "2") (pinfunction "2_2") (pintype "passive"))
      (node (ref "R166") (pin "2") (pinfunction "2_2") (pintype "passive"))
      (node (ref "R167") (pin "2") (pinfunction "2_2") (pintype "passive"))
      (node (ref "R172") (pin "2") (pinfunction "2_2") (pintype "passive"))
      (node (ref "R32") (pin "2") (pinfunction "2_2") (pintype "passive"))
      (node (ref "R41") (pin "1") (pinfunction "1_1") (pintype "passive"))
      (node (ref "U25") (pin "41") (pinfunction "GND_41") (pintype "passive"))
      (node (ref "X3") (pin "2") (pinfunction "GND_2") (pintype "passive"))
      (node (ref "X3") (pin "4") (pinfunction "GND_4") (pintype "passive"))
    )
    (net (code "44") (name "Net-(C130-Pad2)") (class "Default")
      (node (ref "C130") (pin "2") (pinfunction "2_2") (pintype "passive"))
      (node (ref "J21") (pin "P1") (pinfunction "P1_P1") (pintype "passive"))
    )
    (net (code "45") (name "Net-(J21-Pad12)") (class "Default")
      (node (ref "J21") (pin "12") (pintype "passive"))
      (node (ref "R32") (pin "1") (pinfunction "1_1") (pintype "passive"))
    )
    (net (code "46") (name "Net-(J21-Pad14)") (class "Default")
      (node (ref "J21") (pin "14") (pintype "passive"))
      (node (ref "R40") (pin "2") (pinfunction "2_2") (pintype "passive"))
    )
    (net (code "47") (name "Net-(U25-INTB{slash}PMEB)") (class "Default")
      (node (ref "R142") (pin "1") (pinfunction "1_1") (pintype "passive"))
      (node (ref "U25") (pin "31") (pinfunction "INTB/PMEB_31") (pintype "passive"))
    )
    (net (code "48") (name "VCC1V8_SYS") (class "Default")
      (node (ref "R157") (pin "1") (pinfunction "1_1") (pintype "passive"))
    )
    (net (code "49") (name "VCC3V3_PHY1") (class "Default")
      (node (ref "C146") (pin "2") (pinfunction "2_2") (pintype "passive"))
      (node (ref "C147") (pin "2") (pinfunction "2_2") (pintype "passive"))
      (node (ref "C148") (pin "2") (pinfunction "2_2") (pintype "passive"))
      (node (ref "C149") (pin "2") (pinfunction "2_2") (pintype "passive"))
      (node (ref "R162") (pin "2") (pinfunction "2_2") (pintype "passive"))
      (node (ref "R164") (pin "2") (pinfunction "2_2") (pintype "passive"))
      (node (ref "R169") (pin "2") (pinfunction "2_2") (pintype "passive"))
      (node (ref "R170") (pin "2") (pinfunction "2_2") (pintype "passive"))
      (node (ref "R171") (pin "2") (pinfunction "2_2") (pintype "passive"))
      (node (ref "R40") (pin "1") (pinfunction "1_1") (pintype "passive"))
      (node (ref "U25") (pin "11") (pinfunction "AVDD33_11") (pintype "passive"))
      (node (ref "U25") (pin "29") (pinfunction "DVDD33_29") (pintype "passive"))
      (node (ref "U25") (pin "40") (pinfunction "AVDD33_40") (pintype "passive"))
    )
    (net (code "50") (name "VCC3V3_SYS") (class "Default")
      (node (ref "Q10") (pin "1") (pinfunction "G_1") (pintype "passive"))
      (node (ref "Q11") (pin "1") (pinfunction "G_1") (pintype "passive"))
      (node (ref "R152") (pin "1") (pinfunction "1_1") (pintype "passive"))
      (node (ref "R162") (pin "1") (pinfunction "1_1") (pintype "passive"))
      (node (ref "R163") (pin "2") (pinfunction "2_2") (pintype "passive"))
      (node (ref "R168") (pin "2") (pinfunction "2_2") (pintype "passive"))
    )
    (net (code "51") (name "VCCIO_PHY1") (class "Default")
      (node (ref "C140") (pin "2") (pinfunction "2_2") (pintype "passive"))
      (node (ref "C141") (pin "2") (pinfunction "2_2") (pintype "passive"))
      (node (ref "R153") (pin "2") (pinfunction "2_2") (pintype "passive"))
      (node (ref "R156") (pin "2") (pinfunction "2_2") (pintype "passive"))
      (node (ref "R157") (pin "2") (pinfunction "2_2") (pintype "passive"))
      (node (ref "R165") (pin "2") (pinfunction "2_2") (pintype "passive"))
      (node (ref "U25") (pin "28") (pinfunction "DVDD_RG_28") (pintype "passive"))
    )
    (net (code "52") (name "VDD_PHY1") (class "Default")
      (node (ref "C150") (pin "2") (pinfunction "2_2") (pintype "passive"))
      (node (ref "C152") (pin "2") (pinfunction "2_2") (pintype "passive"))
      (node (ref "C153") (pin "2") (pinfunction "2_2") (pintype "passive"))
      (node (ref "C154") (pin "2") (pinfunction "2_2") (pintype "passive"))
      (node (ref "C155") (pin "2") (pinfunction "2_2") (pintype "passive"))
      (node (ref "L6") (pin "2") (pinfunction "2_2") (pintype "passive"))
      (node (ref "U25") (pin "21") (pinfunction "DVDD10_21") (pintype "passive"))
      (node (ref "U25") (pin "3") (pinfunction "AVDD10_3") (pintype "passive"))
      (node (ref "U25") (pin "38") (pinfunction "AVDD10_38") (pintype "passive"))
      (node (ref "U25") (pin "8") (pinfunction "AVDD10_8") (pintype "passive"))
    )
    (net (code "53") (name "unconnected-(J1 Part-E-ETH1_REFCLKO_25M-Pad262)") (class "Default")
      (node (ref "J1 Part-") (pin "262") (pinfunction "ETH1_REFCLKO_25M_262") (pintype "passive+no_connect"))
    )
  )
)
